# lap_counter_V1_2.net
KiCad netlist of a schematic drawn in EAGLE
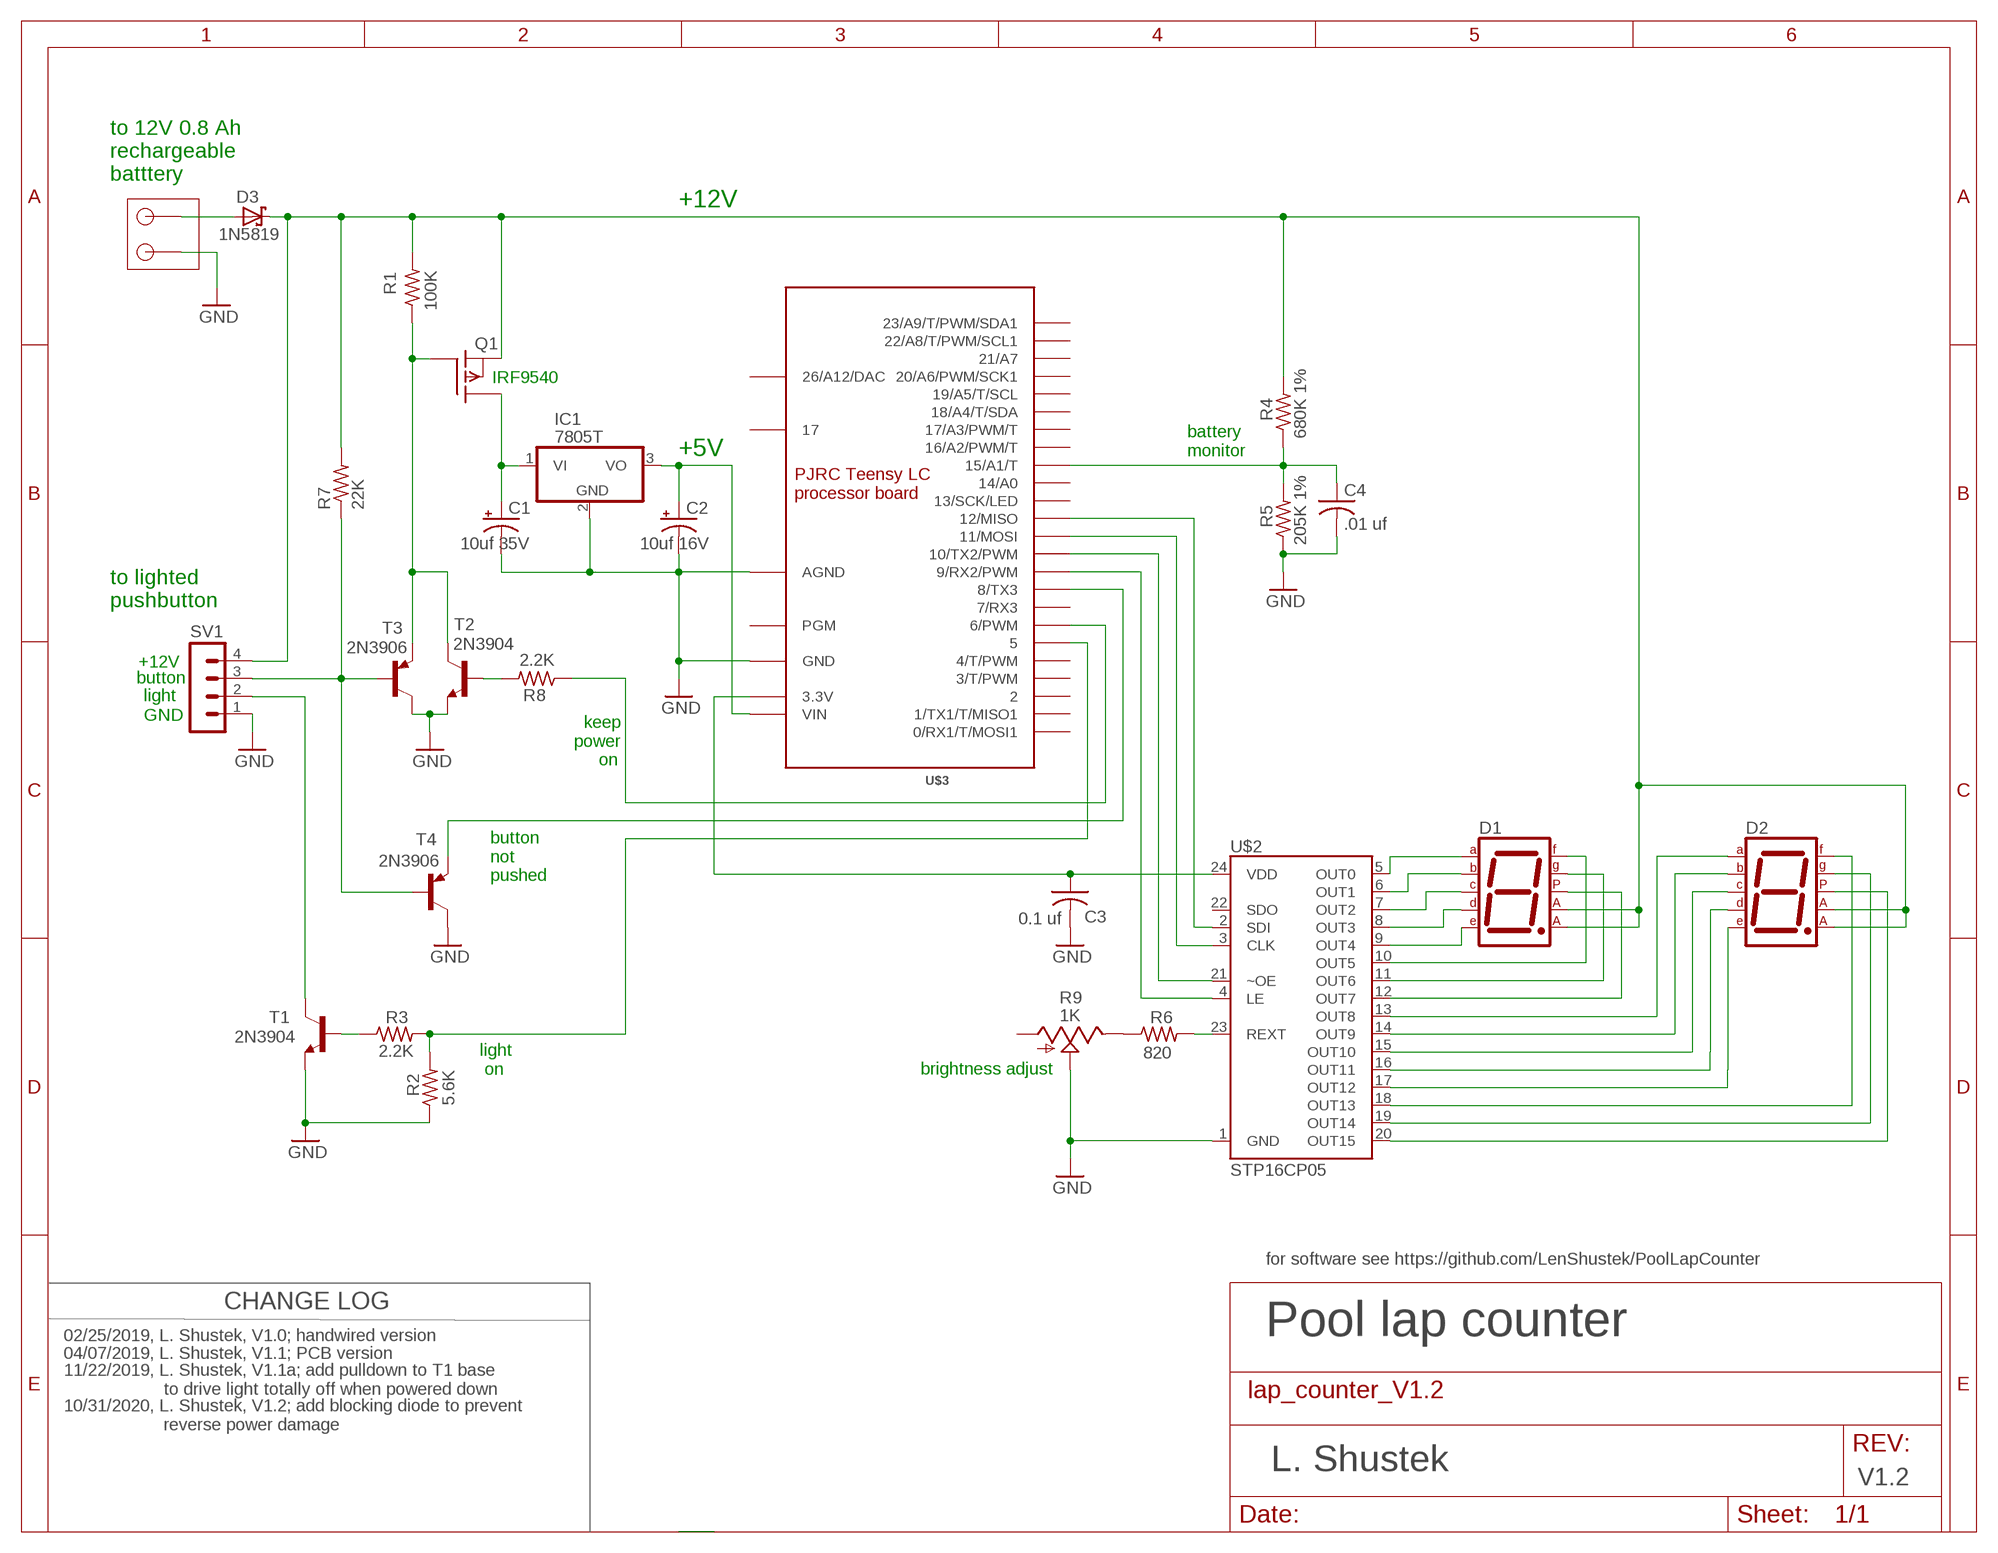
[diagram p0: schematic, sheet 1]

(export (version "E")
  (design (tool "Eeschema 10.0.6"))
  (components
    (comp (ref "C1")
      (value "10uf 35V")
      (footprint "eagle-import:E2,5-6")
      (libsource (lib "eagle-import") (part "CPOL-USE2.5-6"))
    )
    (comp (ref "C2")
      (value "10uf 16V")
      (footprint "eagle-import:E2,5-6")
      (libsource (lib "eagle-import") (part "CPOL-USE2.5-6"))
    )
    (comp (ref "C3")
      (value "0.1 uf")
      (footprint "eagle-import:C025-030X050")
      (libsource (lib "eagle-import") (part "C-US025-030X050"))
    )
    (comp (ref "C4")
      (value ".01 uf")
      (footprint "eagle-import:C025-030X050")
      (libsource (lib "eagle-import") (part "C-US025-030X050"))
    )
    (comp (ref "D1")
      (value "7SEG-CA")
      (footprint "eagle-import:7SEG-13")
      (libsource (lib "eagle-import") (part "7SEG-CA"))
    )
    (comp (ref "D2")
      (value "7SEG-CA")
      (footprint "eagle-import:7SEG-13")
      (libsource (lib "eagle-import") (part "7SEG-CA"))
    )
    (comp (ref "D3")
      (value "1N5819")
      (footprint "eagle-import:DO41-10")
      (libsource (lib "eagle-import") (part "SCHOTTKY-DIODEDO41"))
    )
    (comp (ref "IC1")
      (value "7805T")
      (footprint "eagle-import:TO220H")
      (libsource (lib "eagle-import") (part "78T05"))
    )
    (comp (ref "Q1")
      (value "IRF9530")
      (footprint "eagle-import:TO220")
      (libsource (lib "eagle-import") (part "IRF9530"))
    )
    (comp (ref "R1")
      (value "100K")
      (footprint "eagle-import:0207_10")
      (libsource (lib "eagle-import") (part "R-US_0207/10"))
    )
    (comp (ref "R2")
      (value "5.6K")
      (footprint "eagle-import:0207_10")
      (libsource (lib "eagle-import") (part "R-US_0207/10"))
    )
    (comp (ref "R3")
      (value "2.2K")
      (footprint "eagle-import:0207_10")
      (libsource (lib "eagle-import") (part "R-US_0207/10"))
    )
    (comp (ref "R4")
      (value "680K 1%")
      (footprint "eagle-import:0207_10")
      (libsource (lib "eagle-import") (part "R-US_0207/10"))
    )
    (comp (ref "R5")
      (value "205K 1%")
      (footprint "eagle-import:0207_10")
      (libsource (lib "eagle-import") (part "R-US_0207/10"))
    )
    (comp (ref "R6")
      (value "820")
      (footprint "eagle-import:0207_10")
      (libsource (lib "eagle-import") (part "R-US_0207/10"))
    )
    (comp (ref "R7")
      (value "22K")
      (footprint "eagle-import:0207_10")
      (libsource (lib "eagle-import") (part "R-US_0207/10"))
    )
    (comp (ref "R8")
      (value "2.2K")
      (footprint "eagle-import:0207_10")
      (libsource (lib "eagle-import") (part "R-US_0207/10"))
    )
    (comp (ref "R9")
      (value "1K")
      (footprint "eagle-import:B25P")
      (libsource (lib "eagle-import") (part "TRIM_US-B25P"))
    )
    (comp (ref "SV1")
      (value "MA04-1")
      (footprint "eagle-import:MA04-1")
      (libsource (lib "eagle-import") (part "MA04-1"))
    )
    (comp (ref "T1")
      (value "2N3904")
      (footprint "eagle-import:TO92-EBC-OVAL")
      (libsource (lib "eagle-import") (part "2N2222"))
    )
    (comp (ref "T2")
      (value "2N3904")
      (footprint "eagle-import:TO92-EBC-OVAL")
      (libsource (lib "eagle-import") (part "2N2222"))
    )
    (comp (ref "T3")
      (value "2N3906")
      (footprint "eagle-import:TO92-EBC-OVAL")
      (libsource (lib "eagle-import") (part "2N2907"))
    )
    (comp (ref "T4")
      (value "2N3906")
      (footprint "eagle-import:TO92-EBC-OVAL")
      (libsource (lib "eagle-import") (part "2N2907"))
    )
    (comp (ref "U$1")
      (value "CONNECTOR-2PIN")
      (footprint "eagle-import:CONNECTOR-2PIN-5MM")
      (libsource (lib "eagle-import") (part "CONNECTOR-2PIN"))
    )
    (comp (ref "U$2")
      (value "STP16CP05")
      (footprint "eagle-import:SO-24DW")
      (libsource (lib "eagle-import") (part "STP16CP05"))
    )
    (comp (ref "U$3")
      (value "TEENSY_LC_OUTER_ROW")
      (footprint "eagle-import:TEENSY3-OUTER_ROW")
      (libsource (lib "eagle-import") (part "TEENSY_LC_OUTER_ROW"))
    )
  )
  (nets
    (net (code "1") (name "/26{slash}A12{slash}DAC") (class "Default")
      (node (ref "U$3") (pin "RESET/DAC") (pinfunction "26/A12/DAC_RESET/DAC") (pintype "power_in"))
    )
    (net (code "2") (name "GND") (class "Default")
      (node (ref "C1") (pin "-") (pinfunction "-_-") (pintype "passive"))
      (node (ref "C2") (pin "-") (pinfunction "-_-") (pintype "passive"))
      (node (ref "C3") (pin "2") (pinfunction "2_2") (pintype "passive"))
      (node (ref "C4") (pin "2") (pinfunction "2_2") (pintype "passive"))
      (node (ref "IC1") (pin "2") (pinfunction "GND_2") (pintype "passive"))
      (node (ref "R2") (pin "1") (pinfunction "1_1") (pintype "passive"))
      (node (ref "R5") (pin "1") (pinfunction "1_1") (pintype "passive"))
      (node (ref "R9") (pin "S") (pinfunction "S_S") (pintype "passive"))
      (node (ref "SV1") (pin "1") (pinfunction "1_1") (pintype "passive"))
      (node (ref "T1") (pin "E") (pinfunction "E_E") (pintype "passive"))
      (node (ref "T2") (pin "E") (pinfunction "E_E") (pintype "passive"))
      (node (ref "T3") (pin "C") (pinfunction "C_C") (pintype "passive"))
      (node (ref "T4") (pin "C") (pinfunction "C_C") (pintype "passive"))
      (node (ref "U$1") (pin "P$1") (pinfunction "P$1_P$1") (pintype "bidirectional"))
      (node (ref "U$2") (pin "1") (pinfunction "GND_1") (pintype "bidirectional"))
      (node (ref "U$3") (pin "AGND") (pinfunction "AGND_AGND") (pintype "power_in"))
      (node (ref "U$3") (pin "GND") (pinfunction "GND_GND") (pintype "power_in"))
      (node (ref "U$3") (pin "GND1") (pinfunction "GND_GND1") (pintype "power_in"))
    )
    (net (code "3") (name "Net-(D1-A)") (class "Default")
      (node (ref "D1") (pin "7") (pinfunction "A_7") (pintype "passive"))
      (node (ref "U$2") (pin "5") (pinfunction "OUT0_5") (pintype "bidirectional"))
    )
    (net (code "4") (name "Net-(D1-B)") (class "Default")
      (node (ref "D1") (pin "6") (pinfunction "B_6") (pintype "passive"))
      (node (ref "U$2") (pin "6") (pinfunction "OUT1_6") (pintype "bidirectional"))
    )
    (net (code "5") (name "Net-(D1-C)") (class "Default")
      (node (ref "D1") (pin "4") (pinfunction "C_4") (pintype "passive"))
      (node (ref "U$2") (pin "7") (pinfunction "OUT2_7") (pintype "bidirectional"))
    )
    (net (code "6") (name "Net-(D1-CA1)") (class "Default")
      (node (ref "D1") (pin "3") (pinfunction "CA1_3") (pintype "passive"))
      (node (ref "D1") (pin "8") (pinfunction "CA2_8") (pintype "passive"))
      (node (ref "D2") (pin "3") (pinfunction "CA1_3") (pintype "passive"))
      (node (ref "D2") (pin "8") (pinfunction "CA2_8") (pintype "passive"))
      (node (ref "D3") (pin "C") (pinfunction "C_C") (pintype "passive"))
      (node (ref "Q1") (pin "3") (pinfunction "S_3") (pintype "passive"))
      (node (ref "R1") (pin "2") (pinfunction "2_2") (pintype "passive"))
      (node (ref "R4") (pin "2") (pinfunction "2_2") (pintype "passive"))
      (node (ref "R7") (pin "2") (pinfunction "2_2") (pintype "passive"))
      (node (ref "SV1") (pin "4") (pinfunction "4_4") (pintype "passive"))
    )
    (net (code "7") (name "Net-(D1-D)") (class "Default")
      (node (ref "D1") (pin "2") (pinfunction "D_2") (pintype "passive"))
      (node (ref "U$2") (pin "8") (pinfunction "OUT3_8") (pintype "bidirectional"))
    )
    (net (code "8") (name "Net-(D1-DP)") (class "Default")
      (node (ref "D1") (pin "5") (pinfunction "DP_5") (pintype "passive"))
      (node (ref "U$2") (pin "12") (pinfunction "OUT7_12") (pintype "bidirectional"))
    )
    (net (code "9") (name "Net-(D1-E)") (class "Default")
      (node (ref "D1") (pin "1") (pinfunction "E_1") (pintype "passive"))
      (node (ref "U$2") (pin "9") (pinfunction "OUT4_9") (pintype "bidirectional"))
    )
    (net (code "10") (name "Net-(D1-F)") (class "Default")
      (node (ref "D1") (pin "9") (pinfunction "F_9") (pintype "passive"))
      (node (ref "U$2") (pin "10") (pinfunction "OUT5_10") (pintype "bidirectional"))
    )
    (net (code "11") (name "Net-(D1-G)") (class "Default")
      (node (ref "D1") (pin "10") (pinfunction "G_10") (pintype "passive"))
      (node (ref "U$2") (pin "11") (pinfunction "OUT6_11") (pintype "bidirectional"))
    )
    (net (code "12") (name "Net-(D2-A)") (class "Default")
      (node (ref "D2") (pin "7") (pinfunction "A_7") (pintype "passive"))
      (node (ref "U$2") (pin "13") (pinfunction "OUT8_13") (pintype "bidirectional"))
    )
    (net (code "13") (name "Net-(D2-B)") (class "Default")
      (node (ref "D2") (pin "6") (pinfunction "B_6") (pintype "passive"))
      (node (ref "U$2") (pin "14") (pinfunction "OUT9_14") (pintype "bidirectional"))
    )
    (net (code "14") (name "Net-(D2-C)") (class "Default")
      (node (ref "D2") (pin "4") (pinfunction "C_4") (pintype "passive"))
      (node (ref "U$2") (pin "15") (pinfunction "OUT10_15") (pintype "bidirectional"))
    )
    (net (code "15") (name "Net-(D2-D)") (class "Default")
      (node (ref "D2") (pin "2") (pinfunction "D_2") (pintype "passive"))
      (node (ref "U$2") (pin "16") (pinfunction "OUT11_16") (pintype "bidirectional"))
    )
    (net (code "16") (name "Net-(D2-DP)") (class "Default")
      (node (ref "D2") (pin "5") (pinfunction "DP_5") (pintype "passive"))
      (node (ref "U$2") (pin "20") (pinfunction "OUT15_20") (pintype "bidirectional"))
    )
    (net (code "17") (name "Net-(D2-E)") (class "Default")
      (node (ref "D2") (pin "1") (pinfunction "E_1") (pintype "passive"))
      (node (ref "U$2") (pin "17") (pinfunction "OUT12_17") (pintype "bidirectional"))
    )
    (net (code "18") (name "Net-(D2-F)") (class "Default")
      (node (ref "D2") (pin "9") (pinfunction "F_9") (pintype "passive"))
      (node (ref "U$2") (pin "18") (pinfunction "OUT13_18") (pintype "bidirectional"))
    )
    (net (code "19") (name "Net-(D2-G)") (class "Default")
      (node (ref "D2") (pin "10") (pinfunction "G_10") (pintype "passive"))
      (node (ref "U$2") (pin "19") (pinfunction "OUT14_19") (pintype "bidirectional"))
    )
    (net (code "20") (name "Net-(D3-PadA)") (class "Default")
      (node (ref "D3") (pin "A") (pinfunction "A_A") (pintype "passive"))
      (node (ref "U$1") (pin "P$2") (pinfunction "P$2_P$2") (pintype "bidirectional"))
    )
    (net (code "21") (name "Net-(IC1-VI)") (class "Default")
      (node (ref "C1") (pin "+") (pinfunction "+_+") (pintype "passive"))
      (node (ref "IC1") (pin "1") (pinfunction "VI_1") (pintype "input"))
      (node (ref "Q1") (pin "2") (pinfunction "D_2") (pintype "passive"))
    )
    (net (code "22") (name "Net-(IC1-VO)") (class "Default")
      (node (ref "C2") (pin "+") (pinfunction "+_+") (pintype "passive"))
      (node (ref "IC1") (pin "3") (pinfunction "VO_3") (pintype "passive"))
      (node (ref "U$3") (pin "VIN") (pinfunction "VIN_VIN") (pintype "power_in"))
    )
    (net (code "23") (name "Net-(Q1-G)") (class "Default")
      (node (ref "Q1") (pin "1") (pinfunction "G_1") (pintype "passive"))
      (node (ref "R1") (pin "1") (pinfunction "1_1") (pintype "passive"))
      (node (ref "T2") (pin "C") (pinfunction "C_C") (pintype "passive"))
      (node (ref "T3") (pin "E") (pinfunction "E_E") (pintype "passive"))
    )
    (net (code "24") (name "Net-(R2-Pad2)") (class "Default")
      (node (ref "R2") (pin "2") (pinfunction "2_2") (pintype "passive"))
      (node (ref "R3") (pin "2") (pinfunction "2_2") (pintype "passive"))
      (node (ref "U$3") (pin "5") (pinfunction "5_5") (pintype "bidirectional"))
    )
    (net (code "25") (name "Net-(R3-Pad1)") (class "Default")
      (node (ref "R3") (pin "1") (pinfunction "1_1") (pintype "passive"))
      (node (ref "T1") (pin "B") (pinfunction "B_B") (pintype "passive"))
    )
    (net (code "26") (name "Net-(R6-Pad1)") (class "Default")
      (node (ref "R6") (pin "1") (pinfunction "1_1") (pintype "passive"))
      (node (ref "R9") (pin "E") (pinfunction "E_E") (pintype "passive"))
    )
    (net (code "27") (name "Net-(R7-Pad1)") (class "Default")
      (node (ref "R7") (pin "1") (pinfunction "1_1") (pintype "passive"))
      (node (ref "SV1") (pin "3") (pinfunction "3_3") (pintype "passive"))
      (node (ref "T3") (pin "B") (pinfunction "B_B") (pintype "passive"))
      (node (ref "T4") (pin "B") (pinfunction "B_B") (pintype "passive"))
    )
    (net (code "28") (name "Net-(R8-Pad2)") (class "Default")
      (node (ref "R8") (pin "2") (pinfunction "2_2") (pintype "passive"))
      (node (ref "T2") (pin "B") (pinfunction "B_B") (pintype "passive"))
    )
    (net (code "29") (name "Net-(SV1-Pad2)") (class "Default")
      (node (ref "SV1") (pin "2") (pinfunction "2_2") (pintype "passive"))
      (node (ref "T1") (pin "C") (pinfunction "C_C") (pintype "passive"))
    )
    (net (code "30") (name "Net-(U$2-CLK)") (class "Default")
      (node (ref "U$2") (pin "3") (pinfunction "CLK_3") (pintype "bidirectional"))
      (node (ref "U$3") (pin "11") (pinfunction "11/MOSI_11") (pintype "bidirectional"))
    )
    (net (code "31") (name "Net-(U$2-LE)") (class "Default")
      (node (ref "U$2") (pin "4") (pinfunction "LE_4") (pintype "bidirectional"))
      (node (ref "U$3") (pin "9") (pinfunction "9/RX2/PWM_9") (pintype "bidirectional"))
    )
    (net (code "32") (name "Net-(U$2-REXT)") (class "Default")
      (node (ref "R6") (pin "2") (pinfunction "2_2") (pintype "passive"))
      (node (ref "U$2") (pin "23") (pinfunction "REXT_23") (pintype "bidirectional"))
    )
    (net (code "33") (name "Net-(U$2-SDI)") (class "Default")
      (node (ref "U$2") (pin "2") (pinfunction "SDI_2") (pintype "bidirectional"))
      (node (ref "U$3") (pin "12") (pinfunction "12/MISO_12") (pintype "bidirectional"))
    )
    (net (code "34") (name "Net-(U$2-VDD)") (class "Default")
      (node (ref "C3") (pin "1") (pinfunction "1_1") (pintype "passive"))
      (node (ref "U$2") (pin "24") (pinfunction "VDD_24") (pintype "bidirectional"))
      (node (ref "U$3") (pin "3.3V") (pinfunction "3.3V_3.3V") (pintype "power_in"))
      (node (ref "U$3") (pin "3.3V1") (pinfunction "3.3V_3.3V1") (pintype "power_in"))
    )
    (net (code "35") (name "Net-(U$2-~{OE})") (class "Default")
      (node (ref "U$2") (pin "21") (pinfunction "~{OE}_21") (pintype "bidirectional"))
      (node (ref "U$3") (pin "10") (pinfunction "10/TX2/PWM_10") (pintype "bidirectional"))
    )
    (net (code "36") (name "Net-(U$3-6{slash}PWM)") (class "Default")
      (node (ref "R8") (pin "1") (pinfunction "1_1") (pintype "passive"))
      (node (ref "U$3") (pin "6") (pinfunction "6/PWM_6") (pintype "bidirectional"))
    )
    (net (code "37") (name "Net-(U$3-8{slash}TX3)") (class "Default")
      (node (ref "T4") (pin "E") (pinfunction "E_E") (pintype "passive"))
      (node (ref "U$3") (pin "8") (pinfunction "8/TX3_8") (pintype "bidirectional"))
    )
    (net (code "38") (name "Net-(U$3-15{slash}A1{slash}T)") (class "Default")
      (node (ref "C4") (pin "1") (pinfunction "1_1") (pintype "passive"))
      (node (ref "R4") (pin "1") (pinfunction "1_1") (pintype "passive"))
      (node (ref "R5") (pin "2") (pinfunction "2_2") (pintype "passive"))
      (node (ref "U$3") (pin "15/A1") (pinfunction "15/A1/T_15/A1") (pintype "bidirectional"))
    )
    (net (code "39") (name "unconnected-(R9-PadA)") (class "Default")
      (node (ref "R9") (pin "A") (pinfunction "A_A") (pintype "passive"))
    )
    (net (code "40") (name "unconnected-(U$2-SDO-Pad22)") (class "Default")
      (node (ref "U$2") (pin "22") (pinfunction "SDO_22") (pintype "bidirectional"))
    )
    (net (code "41") (name "unconnected-(U$3-0{slash}RX1{slash}T{slash}MOSI1-Pad0)") (class "Default")
      (node (ref "U$3") (pin "0") (pinfunction "0/RX1/T/MOSI1_0") (pintype "bidirectional"))
    )
    (net (code "42") (name "unconnected-(U$3-1{slash}TX1{slash}T{slash}MISO1-Pad1)") (class "Default")
      (node (ref "U$3") (pin "1") (pinfunction "1/TX1/T/MISO1_1") (pintype "bidirectional"))
    )
    (net (code "43") (name "unconnected-(U$3-3{slash}T{slash}PWM-Pad3)") (class "Default")
      (node (ref "U$3") (pin "3") (pinfunction "3/T/PWM_3") (pintype "bidirectional"))
    )
    (net (code "44") (name "unconnected-(U$3-4{slash}T{slash}PWM-Pad4)") (class "Default")
      (node (ref "U$3") (pin "4") (pinfunction "4/T/PWM_4") (pintype "bidirectional"))
    )
    (net (code "45") (name "unconnected-(U$3-7{slash}RX3-Pad7)") (class "Default")
      (node (ref "U$3") (pin "7") (pinfunction "7/RX3_7") (pintype "bidirectional"))
    )
    (net (code "46") (name "unconnected-(U$3-13{slash}SCK{slash}LED-Pad13)") (class "Default")
      (node (ref "U$3") (pin "13") (pinfunction "13/SCK/LED_13") (pintype "bidirectional"))
    )
    (net (code "47") (name "unconnected-(U$3-16{slash}A2{slash}PWM{slash}T-Pad16{slash}A2)") (class "Default")
      (node (ref "U$3") (pin "16/A2") (pinfunction "16/A2/PWM/T_16/A2") (pintype "bidirectional"))
    )
    (net (code "48") (name "unconnected-(U$3-17-PadVBAT)") (class "Default")
      (node (ref "U$3") (pin "VBAT") (pinfunction "17_VBAT") (pintype "bidirectional"))
    )
    (net (code "49") (name "unconnected-(U$3-17{slash}A3{slash}PWM{slash}T-Pad17{slash}A3)") (class "Default")
      (node (ref "U$3") (pin "17/A3") (pinfunction "17/A3/PWM/T_17/A3") (pintype "bidirectional"))
    )
    (net (code "50") (name "unconnected-(U$3-18{slash}A4{slash}T{slash}SDA-Pad18{slash}A4)") (class "Default")
      (node (ref "U$3") (pin "18/A4") (pinfunction "18/A4/T/SDA_18/A4") (pintype "bidirectional"))
    )
    (net (code "51") (name "unconnected-(U$3-19{slash}A5{slash}T{slash}SCL-Pad19{slash}A5)") (class "Default")
      (node (ref "U$3") (pin "19/A5") (pinfunction "19/A5/T/SCL_19/A5") (pintype "bidirectional"))
    )
    (net (code "52") (name "unconnected-(U$3-20{slash}A6{slash}PWM{slash}SCK1-Pad20{slash}A6)") (class "Default")
      (node (ref "U$3") (pin "20/A6") (pinfunction "20/A6/PWM/SCK1_20/A6") (pintype "bidirectional"))
    )
    (net (code "53") (name "unconnected-(U$3-22{slash}A8{slash}T{slash}PWM{slash}SCL1-Pad22{slash}A8)") (class "Default")
      (node (ref "U$3") (pin "22/A8") (pinfunction "22/A8/T/PWM/SCL1_22/A8") (pintype "bidirectional"))
    )
    (net (code "54") (name "unconnected-(U$3-23{slash}A9{slash}T{slash}PWM{slash}SDA1-Pad23{slash}A9)") (class "Default")
      (node (ref "U$3") (pin "23/A9") (pinfunction "23/A9/T/PWM/SDA1_23/A9") (pintype "bidirectional"))
    )
    (net (code "55") (name "unconnected-(U$3-Pad2)") (class "Default")
      (node (ref "U$3") (pin "2") (pinfunction "2_2") (pintype "bidirectional"))
    )
    (net (code "56") (name "unconnected-(U$3-Pad14{slash}A0)") (class "Default")
      (node (ref "U$3") (pin "14/A0") (pinfunction "14/A0_14/A0") (pintype "bidirectional"))
    )
    (net (code "57") (name "unconnected-(U$3-Pad21{slash}A7)") (class "Default")
      (node (ref "U$3") (pin "21/A7") (pinfunction "21/A7_21/A7") (pintype "bidirectional"))
    )
    (net (code "58") (name "unconnected-(U$3-PadPGM)") (class "Default")
      (node (ref "U$3") (pin "PGM") (pinfunction "PGM_PGM") (pintype "bidirectional"))
    )
  )
)
